# PickupDriverV3_3.net
KiCad netlist of a schematic drawn in EAGLE
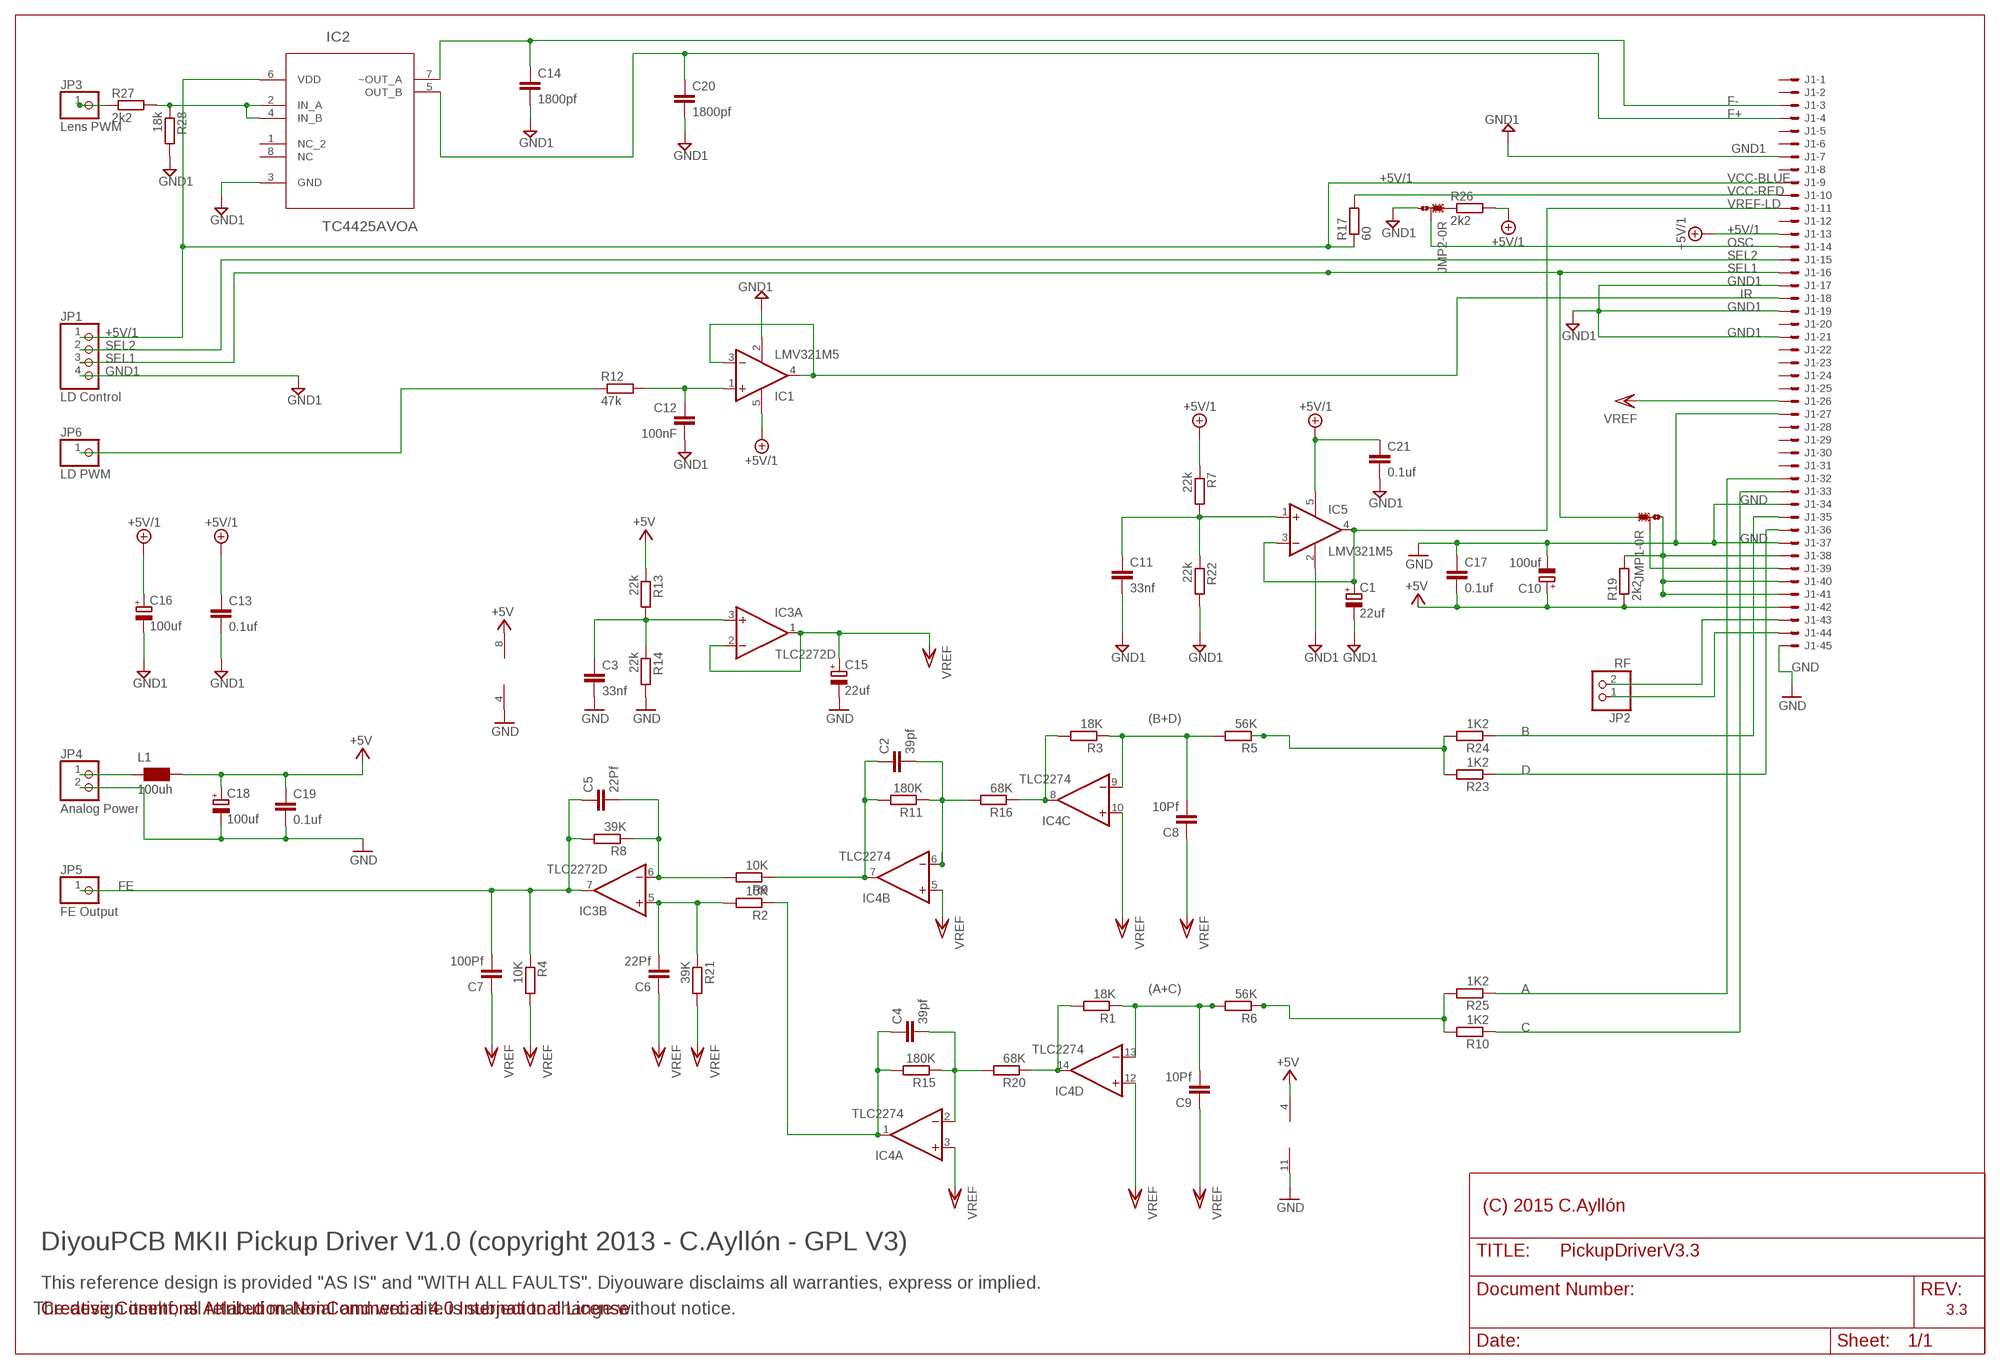
[diagram p0: schematic, sheet 1]

(export (version "E")
  (design (tool "Eeschema 10.0.6"))
  (components
    (comp (ref "C1")
      (value "22uf")
      (footprint "eagle-import:SMC_C")
      (libsource (lib "eagle-import") (part "CPOL-EUSMCC"))
    )
    (comp (ref "C2")
      (value "39pf")
      (footprint "eagle-import:C1206K")
      (libsource (lib "eagle-import") (part "C-EUC1206K"))
    )
    (comp (ref "C3")
      (value "33nf")
      (footprint "eagle-import:C1206K")
      (libsource (lib "eagle-import") (part "resistor_C-EUC1206K"))
    )
    (comp (ref "C4")
      (value "39pf")
      (footprint "eagle-import:C1206K")
      (libsource (lib "eagle-import") (part "C-EUC1206K"))
    )
    (comp (ref "C5")
      (value "22Pf")
      (footprint "eagle-import:C1206K")
      (libsource (lib "eagle-import") (part "C-EUC1206K"))
    )
    (comp (ref "C6")
      (value "22Pf")
      (footprint "eagle-import:C1206K")
      (libsource (lib "eagle-import") (part "C-EUC1206K"))
    )
    (comp (ref "C7")
      (value "100Pf")
      (footprint "eagle-import:C1206K")
      (libsource (lib "eagle-import") (part "C-EUC1206K"))
    )
    (comp (ref "C8")
      (value "10Pf")
      (footprint "eagle-import:C1206K")
      (libsource (lib "eagle-import") (part "C-EUC1206K"))
    )
    (comp (ref "C9")
      (value "10Pf")
      (footprint "eagle-import:C1206K")
      (libsource (lib "eagle-import") (part "C-EUC1206K"))
    )
    (comp (ref "C10")
      (value "100uf")
      (footprint "eagle-import:SMC_C")
      (libsource (lib "eagle-import") (part "CPOL-EUSMCC"))
    )
    (comp (ref "C11")
      (value "33nf")
      (footprint "eagle-import:C1206K")
      (libsource (lib "eagle-import") (part "resistor_C-EUC1206K"))
    )
    (comp (ref "C12")
      (value "100nF")
      (footprint "eagle-import:C1206K")
      (libsource (lib "eagle-import") (part "C-EUC1206K"))
    )
    (comp (ref "C13")
      (value "0.1uf")
      (footprint "eagle-import:C1206K")
      (libsource (lib "eagle-import") (part "resistor_C-EUC1206K"))
    )
    (comp (ref "C14")
      (value "1800pf")
      (footprint "eagle-import:C1206K")
      (libsource (lib "eagle-import") (part "C-EUC1206K"))
    )
    (comp (ref "C15")
      (value "22uf")
      (footprint "eagle-import:SMC_C")
      (libsource (lib "eagle-import") (part "CPOL-EUSMCC"))
    )
    (comp (ref "C16")
      (value "100uf")
      (footprint "eagle-import:SMC_C")
      (libsource (lib "eagle-import") (part "CPOL-EUSMCC"))
    )
    (comp (ref "C17")
      (value "0.1uf")
      (footprint "eagle-import:C1206K")
      (libsource (lib "eagle-import") (part "resistor_C-EUC1206K"))
    )
    (comp (ref "C18")
      (value "100uf")
      (footprint "eagle-import:SMC_C")
      (libsource (lib "eagle-import") (part "CPOL-EUSMCC"))
    )
    (comp (ref "C19")
      (value "0.1uf")
      (footprint "eagle-import:C1206K")
      (libsource (lib "eagle-import") (part "resistor_C-EUC1206K"))
    )
    (comp (ref "C20")
      (value "1800pf")
      (footprint "eagle-import:C1206K")
      (libsource (lib "eagle-import") (part "C-EUC1206K"))
    )
    (comp (ref "C21")
      (value "0.1uf")
      (footprint "eagle-import:C1206K")
      (libsource (lib "eagle-import") (part "resistor_C-EUC1206K"))
    )
    (comp (ref "IC1")
      (value "LMV321M5")
      (footprint "eagle-import:SOT23-5")
      (libsource (lib "eagle-import") (part "LMV321?M5"))
    )
    (comp (ref "IC2")
      (value "TC4425AVOA")
      (footprint "eagle-import:SOIC127P600X175-8N")
      (libsource (lib "eagle-import") (part "TC4425AVOA"))
    )
    (comp (ref "IC3")
      (value "TLC2272D")
      (footprint "eagle-import:SO08")
      (libsource (lib "eagle-import") (part "TLC2272D"))
    )
    (comp (ref "IC4")
      (value "TLC2274")
      (footprint "eagle-import:SO14")
      (libsource (lib "eagle-import") (part "TLC274D"))
    )
    (comp (ref "IC5")
      (value "LMV321M5")
      (footprint "eagle-import:SOT23-5")
      (libsource (lib "eagle-import") (part "LMV321?M5"))
    )
    (comp (ref "J1")
      (value "XF2H-4515-1LW")
      (footprint "eagle-import:XF2H-4515-1LW")
      (libsource (lib "eagle-import") (part "XF2-45?15-1LWH"))
    )
    (comp (ref "JMP1")
      (value "0R-JUMPA")
      (footprint "eagle-import:A0R-JMP")
      (libsource (lib "eagle-import") (part "0R-JUMPA"))
    )
    (comp (ref "JMP2")
      (value "0R-JUMPA")
      (footprint "eagle-import:A0R-JMP")
      (libsource (lib "eagle-import") (part "0R-JUMPA"))
    )
    (comp (ref "JP1")
      (value "LD Control")
      (footprint "eagle-import:1X04")
      (libsource (lib "eagle-import") (part "PINHD-1X4"))
    )
    (comp (ref "JP2")
      (value "RF")
      (footprint "eagle-import:1X02")
      (libsource (lib "eagle-import") (part "PINHD-1X2"))
    )
    (comp (ref "JP3")
      (value "Lens PWM")
      (footprint "eagle-import:1X01")
      (libsource (lib "eagle-import") (part "PINHD-1X1"))
    )
    (comp (ref "JP4")
      (value "Analog Power")
      (footprint "eagle-import:1X02")
      (libsource (lib "eagle-import") (part "PINHD-1X2"))
    )
    (comp (ref "JP5")
      (value "FE Output")
      (footprint "eagle-import:1X01")
      (libsource (lib "eagle-import") (part "PINHD-1X1"))
    )
    (comp (ref "JP6")
      (value "LD PWM")
      (footprint "eagle-import:1X01")
      (libsource (lib "eagle-import") (part "PINHD-1X1"))
    )
    (comp (ref "L1")
      (value "100uh")
      (footprint "eagle-import:CHOKE-100UH-1")
      (libsource (lib "eagle-import") (part "CHOKE-100UH"))
    )
    (comp (ref "R1")
      (value "18K")
      (footprint "eagle-import:R1206")
      (libsource (lib "eagle-import") (part "R-EU_R1206"))
    )
    (comp (ref "R2")
      (value "10K")
      (footprint "eagle-import:R1206")
      (libsource (lib "eagle-import") (part "R-EU_R1206"))
    )
    (comp (ref "R3")
      (value "18K")
      (footprint "eagle-import:R1206")
      (libsource (lib "eagle-import") (part "R-EU_R1206"))
    )
    (comp (ref "R4")
      (value "10K")
      (footprint "eagle-import:R1206")
      (libsource (lib "eagle-import") (part "R-EU_R1206"))
    )
    (comp (ref "R5")
      (value "56K")
      (footprint "eagle-import:R1206")
      (libsource (lib "eagle-import") (part "R-EU_R1206"))
    )
    (comp (ref "R6")
      (value "56K")
      (footprint "eagle-import:R1206")
      (libsource (lib "eagle-import") (part "R-EU_R1206"))
    )
    (comp (ref "R7")
      (value "22k")
      (footprint "eagle-import:R1206")
      (libsource (lib "eagle-import") (part "R-EU_R1206"))
    )
    (comp (ref "R8")
      (value "39K")
      (footprint "eagle-import:R1206")
      (libsource (lib "eagle-import") (part "R-EU_R1206"))
    )
    (comp (ref "R9")
      (value "10K")
      (footprint "eagle-import:R1206")
      (libsource (lib "eagle-import") (part "R-EU_R1206"))
    )
    (comp (ref "R10")
      (value "1K2")
      (footprint "eagle-import:R1206")
      (libsource (lib "eagle-import") (part "R-EU_R1206"))
    )
    (comp (ref "R11")
      (value "180K")
      (footprint "eagle-import:R1206")
      (libsource (lib "eagle-import") (part "R-EU_R1206"))
    )
    (comp (ref "R12")
      (value "47k")
      (footprint "eagle-import:R1206")
      (libsource (lib "eagle-import") (part "R-EU_R1206"))
    )
    (comp (ref "R13")
      (value "22k")
      (footprint "eagle-import:R1206")
      (libsource (lib "eagle-import") (part "R-EU_R1206"))
    )
    (comp (ref "R14")
      (value "22k")
      (footprint "eagle-import:R1206")
      (libsource (lib "eagle-import") (part "R-EU_R1206"))
    )
    (comp (ref "R15")
      (value "180K")
      (footprint "eagle-import:R1206")
      (libsource (lib "eagle-import") (part "R-EU_R1206"))
    )
    (comp (ref "R16")
      (value "68K")
      (footprint "eagle-import:R1206")
      (libsource (lib "eagle-import") (part "R-EU_R1206"))
    )
    (comp (ref "R17")
      (value "60")
      (footprint "eagle-import:R1206")
      (libsource (lib "eagle-import") (part "R-EU_R1206"))
    )
    (comp (ref "R19")
      (value "2k2")
      (footprint "eagle-import:R1206")
      (libsource (lib "eagle-import") (part "R-EU_R1206"))
    )
    (comp (ref "R20")
      (value "68K")
      (footprint "eagle-import:R1206")
      (libsource (lib "eagle-import") (part "R-EU_R1206"))
    )
    (comp (ref "R21")
      (value "39K")
      (footprint "eagle-import:R1206")
      (libsource (lib "eagle-import") (part "R-EU_R1206"))
    )
    (comp (ref "R22")
      (value "22k")
      (footprint "eagle-import:R1206")
      (libsource (lib "eagle-import") (part "R-EU_R1206"))
    )
    (comp (ref "R23")
      (value "1K2")
      (footprint "eagle-import:R1206")
      (libsource (lib "eagle-import") (part "R-EU_R1206"))
    )
    (comp (ref "R24")
      (value "1K2")
      (footprint "eagle-import:R1206")
      (libsource (lib "eagle-import") (part "R-EU_R1206"))
    )
    (comp (ref "R25")
      (value "1K2")
      (footprint "eagle-import:R1206")
      (libsource (lib "eagle-import") (part "R-EU_R1206"))
    )
    (comp (ref "R26")
      (value "2k2")
      (footprint "eagle-import:R1206")
      (libsource (lib "eagle-import") (part "R-EU_R1206"))
    )
    (comp (ref "R27")
      (value "2k2")
      (footprint "eagle-import:R1206")
      (libsource (lib "eagle-import") (part "R-EU_R1206"))
    )
    (comp (ref "R28")
      (value "18k")
      (footprint "eagle-import:R1206")
      (libsource (lib "eagle-import") (part "R-EU_R1206"))
    )
  )
  (nets
    (net (code "1") (name "+5V") (class "Default")
      (node (ref "C10") (pin "+") (pinfunction "+_+") (pintype "passive"))
      (node (ref "C17") (pin "2") (pinfunction "2_2") (pintype "passive"))
      (node (ref "C18") (pin "+") (pinfunction "+_+") (pintype "passive"))
      (node (ref "C19") (pin "1") (pinfunction "1_1") (pintype "passive"))
      (node (ref "IC3") (pin "8") (pinfunction "V+_8") (pintype "power_in"))
      (node (ref "IC4") (pin "4") (pinfunction "V+_4") (pintype "power_in"))
      (node (ref "J1") (pin "42") (pinfunction "MS_42") (pintype "passive"))
      (node (ref "L1") (pin "2") (pinfunction "2_2") (pintype "passive"))
      (node (ref "R13") (pin "1") (pinfunction "1_1") (pintype "passive"))
      (node (ref "R19") (pin "1") (pinfunction "1_1") (pintype "passive"))
    )
    (net (code "2") (name "+5V{slash}1") (class "Default")
      (node (ref "C13") (pin "1") (pinfunction "1_1") (pintype "passive"))
      (node (ref "C16") (pin "+") (pinfunction "+_+") (pintype "passive"))
      (node (ref "C21") (pin "1") (pinfunction "1_1") (pintype "passive"))
      (node (ref "IC1") (pin "5") (pinfunction "V+_5") (pintype "power_in"))
      (node (ref "IC2") (pin "6") (pinfunction "VDD_6") (pintype "power_in"))
      (node (ref "IC5") (pin "5") (pinfunction "V+_5") (pintype "power_in"))
      (node (ref "J1") (pin "13") (pinfunction "MS_13") (pintype "passive"))
      (node (ref "J1") (pin "9") (pinfunction "MS_9") (pintype "passive"))
      (node (ref "JP1") (pin "1") (pinfunction "1_1") (pintype "passive"))
      (node (ref "R17") (pin "1") (pinfunction "1_1") (pintype "passive"))
      (node (ref "R26") (pin "2") (pinfunction "2_2") (pintype "passive"))
      (node (ref "R7") (pin "1") (pinfunction "1_1") (pintype "passive"))
    )
    (net (code "3") (name "/A") (class "Default")
      (node (ref "J1") (pin "32") (pinfunction "MS_32") (pintype "passive"))
      (node (ref "R25") (pin "1") (pinfunction "1_1") (pintype "passive"))
    )
    (net (code "4") (name "/B") (class "Default")
      (node (ref "J1") (pin "35") (pinfunction "MS_35") (pintype "passive"))
      (node (ref "R24") (pin "1") (pinfunction "1_1") (pintype "passive"))
    )
    (net (code "5") (name "/C") (class "Default")
      (node (ref "J1") (pin "33") (pinfunction "MS_33") (pintype "passive"))
      (node (ref "R10") (pin "1") (pinfunction "1_1") (pintype "passive"))
    )
    (net (code "6") (name "/D") (class "Default")
      (node (ref "J1") (pin "36") (pinfunction "MS_36") (pintype "passive"))
      (node (ref "R23") (pin "1") (pinfunction "1_1") (pintype "passive"))
    )
    (net (code "7") (name "/F+") (class "Default")
      (node (ref "C20") (pin "1") (pinfunction "1_1") (pintype "passive"))
      (node (ref "IC2") (pin "5") (pinfunction "OUT_B_5") (pintype "output"))
      (node (ref "J1") (pin "4") (pinfunction "MS_4") (pintype "passive"))
    )
    (net (code "8") (name "/F-") (class "Default")
      (node (ref "C14") (pin "1") (pinfunction "1_1") (pintype "passive"))
      (node (ref "IC2") (pin "7") (pinfunction "~{OUT_A}_7") (pintype "output"))
      (node (ref "J1") (pin "3") (pinfunction "MS_3") (pintype "passive"))
    )
    (net (code "9") (name "/FE") (class "Default")
      (node (ref "C5") (pin "1") (pinfunction "1_1") (pintype "passive"))
      (node (ref "C7") (pin "2") (pinfunction "2_2") (pintype "passive"))
      (node (ref "IC3") (pin "7") (pinfunction "OUT_7") (pintype "output"))
      (node (ref "JP5") (pin "1") (pinfunction "1_1") (pintype "passive"))
      (node (ref "R4") (pin "1") (pinfunction "1_1") (pintype "passive"))
      (node (ref "R8") (pin "2") (pinfunction "2_2") (pintype "passive"))
    )
    (net (code "10") (name "/IR") (class "Default")
      (node (ref "IC1") (pin "3") (pinfunction "-IN_3") (pintype "input"))
      (node (ref "IC1") (pin "4") (pinfunction "OUT_4") (pintype "output"))
      (node (ref "J1") (pin "18") (pinfunction "MS_18") (pintype "passive"))
    )
    (net (code "11") (name "/OSC") (class "Default")
      (node (ref "J1") (pin "14") (pinfunction "MS_14") (pintype "passive"))
      (node (ref "JMP2") (pin "2") (pinfunction "2_2") (pintype "passive"))
    )
    (net (code "12") (name "/SEL1") (class "Default")
      (node (ref "J1") (pin "16") (pinfunction "MS_16") (pintype "passive"))
      (node (ref "JMP1") (pin "1") (pinfunction "1_1") (pintype "passive"))
      (node (ref "JP1") (pin "3") (pinfunction "3_3") (pintype "passive"))
    )
    (net (code "13") (name "/SEL2") (class "Default")
      (node (ref "J1") (pin "15") (pinfunction "MS_15") (pintype "passive"))
      (node (ref "JP1") (pin "2") (pinfunction "2_2") (pintype "passive"))
    )
    (net (code "14") (name "/VREF-LD") (class "Default")
      (node (ref "C1") (pin "+") (pinfunction "+_+") (pintype "passive"))
      (node (ref "IC5") (pin "3") (pinfunction "-IN_3") (pintype "input"))
      (node (ref "IC5") (pin "4") (pinfunction "OUT_4") (pintype "output"))
      (node (ref "J1") (pin "11") (pinfunction "MS_11") (pintype "passive"))
    )
    (net (code "15") (name "GND") (class "Default")
      (node (ref "C10") (pin "-") (pinfunction "-_-") (pintype "passive"))
      (node (ref "C15") (pin "-") (pinfunction "-_-") (pintype "passive"))
      (node (ref "C17") (pin "1") (pinfunction "1_1") (pintype "passive"))
      (node (ref "C18") (pin "-") (pinfunction "-_-") (pintype "passive"))
      (node (ref "C19") (pin "2") (pinfunction "2_2") (pintype "passive"))
      (node (ref "C3") (pin "2") (pinfunction "2_2") (pintype "passive"))
      (node (ref "IC3") (pin "4") (pinfunction "V-_4") (pintype "power_in"))
      (node (ref "IC4") (pin "11") (pinfunction "V-_11") (pintype "power_in"))
      (node (ref "J1") (pin "27") (pinfunction "MS_27") (pintype "passive"))
      (node (ref "J1") (pin "34") (pinfunction "MS_34") (pintype "passive"))
      (node (ref "J1") (pin "37") (pinfunction "MS_37") (pintype "passive"))
      (node (ref "J1") (pin "45") (pinfunction "MS_45") (pintype "passive"))
      (node (ref "JP4") (pin "2") (pinfunction "2_2") (pintype "passive"))
      (node (ref "R14") (pin "2") (pinfunction "2_2") (pintype "passive"))
    )
    (net (code "16") (name "GND1") (class "Default")
      (node (ref "C1") (pin "-") (pinfunction "-_-") (pintype "passive"))
      (node (ref "C11") (pin "2") (pinfunction "2_2") (pintype "passive"))
      (node (ref "C12") (pin "2") (pinfunction "2_2") (pintype "passive"))
      (node (ref "C13") (pin "2") (pinfunction "2_2") (pintype "passive"))
      (node (ref "C14") (pin "2") (pinfunction "2_2") (pintype "passive"))
      (node (ref "C16") (pin "-") (pinfunction "-_-") (pintype "passive"))
      (node (ref "C20") (pin "2") (pinfunction "2_2") (pintype "passive"))
      (node (ref "C21") (pin "2") (pinfunction "2_2") (pintype "passive"))
      (node (ref "IC1") (pin "2") (pinfunction "V-_2") (pintype "power_in"))
      (node (ref "IC2") (pin "3") (pinfunction "GND_3") (pintype "passive"))
      (node (ref "IC5") (pin "2") (pinfunction "V-_2") (pintype "power_in"))
      (node (ref "J1") (pin "17") (pinfunction "MS_17") (pintype "passive"))
      (node (ref "J1") (pin "19") (pinfunction "MS_19") (pintype "passive"))
      (node (ref "J1") (pin "21") (pinfunction "MS_21") (pintype "passive"))
      (node (ref "J1") (pin "7") (pinfunction "MS_7") (pintype "passive"))
      (node (ref "JMP2") (pin "3") (pinfunction "3_3") (pintype "passive"))
      (node (ref "JP1") (pin "4") (pinfunction "4_4") (pintype "passive"))
      (node (ref "R22") (pin "2") (pinfunction "2_2") (pintype "passive"))
      (node (ref "R28") (pin "2") (pinfunction "2_2") (pintype "passive"))
    )
    (net (code "17") (name "Net-(IC1-+IN)") (class "Default")
      (node (ref "C12") (pin "1") (pinfunction "1_1") (pintype "passive"))
      (node (ref "IC1") (pin "1") (pinfunction "+IN_1") (pintype "input"))
      (node (ref "R12") (pin "2") (pinfunction "2_2") (pintype "passive"))
    )
    (net (code "18") (name "Net-(IC2-IN_A)") (class "Default")
      (node (ref "IC2") (pin "2") (pinfunction "IN_A_2") (pintype "input"))
      (node (ref "IC2") (pin "4") (pinfunction "IN_B_4") (pintype "input"))
      (node (ref "R27") (pin "2") (pinfunction "2_2") (pintype "passive"))
      (node (ref "R28") (pin "1") (pinfunction "1_1") (pintype "passive"))
    )
    (net (code "19") (name "Net-(IC3A-+IN)") (class "Default")
      (node (ref "C3") (pin "1") (pinfunction "1_1") (pintype "passive"))
      (node (ref "IC3") (pin "3") (pinfunction "+IN_3") (pintype "input"))
      (node (ref "R13") (pin "2") (pinfunction "2_2") (pintype "passive"))
      (node (ref "R14") (pin "1") (pinfunction "1_1") (pintype "passive"))
    )
    (net (code "20") (name "Net-(IC3B-+IN)") (class "Default")
      (node (ref "C6") (pin "2") (pinfunction "2_2") (pintype "passive"))
      (node (ref "IC3") (pin "5") (pinfunction "+IN_5") (pintype "input"))
      (node (ref "R2") (pin "2") (pinfunction "2_2") (pintype "passive"))
      (node (ref "R21") (pin "1") (pinfunction "1_1") (pintype "passive"))
    )
    (net (code "21") (name "Net-(IC3B--IN)") (class "Default")
      (node (ref "C5") (pin "2") (pinfunction "2_2") (pintype "passive"))
      (node (ref "IC3") (pin "6") (pinfunction "-IN_6") (pintype "input"))
      (node (ref "R8") (pin "1") (pinfunction "1_1") (pintype "passive"))
      (node (ref "R9") (pin "2") (pinfunction "2_2") (pintype "passive"))
    )
    (net (code "22") (name "Net-(IC4A--IN)") (class "Default")
      (node (ref "C4") (pin "2") (pinfunction "2_2") (pintype "passive"))
      (node (ref "IC4") (pin "2") (pinfunction "-IN_2") (pintype "input"))
      (node (ref "R15") (pin "1") (pinfunction "1_1") (pintype "passive"))
      (node (ref "R20") (pin "2") (pinfunction "2_2") (pintype "passive"))
    )
    (net (code "23") (name "Net-(IC4A-OUT)") (class "Default")
      (node (ref "C4") (pin "1") (pinfunction "1_1") (pintype "passive"))
      (node (ref "IC4") (pin "1") (pinfunction "OUT_1") (pintype "output"))
      (node (ref "R15") (pin "2") (pinfunction "2_2") (pintype "passive"))
      (node (ref "R2") (pin "1") (pinfunction "1_1") (pintype "passive"))
    )
    (net (code "24") (name "Net-(IC4B--IN)") (class "Default")
      (node (ref "C2") (pin "2") (pinfunction "2_2") (pintype "passive"))
      (node (ref "IC4") (pin "6") (pinfunction "-IN_6") (pintype "input"))
      (node (ref "R11") (pin "1") (pinfunction "1_1") (pintype "passive"))
      (node (ref "R16") (pin "2") (pinfunction "2_2") (pintype "passive"))
    )
    (net (code "25") (name "Net-(IC4B-OUT)") (class "Default")
      (node (ref "C2") (pin "1") (pinfunction "1_1") (pintype "passive"))
      (node (ref "IC4") (pin "7") (pinfunction "OUT_7") (pintype "output"))
      (node (ref "R11") (pin "2") (pinfunction "2_2") (pintype "passive"))
      (node (ref "R9") (pin "1") (pinfunction "1_1") (pintype "passive"))
    )
    (net (code "26") (name "Net-(IC4C--IN)") (class "Default")
      (node (ref "C8") (pin "2") (pinfunction "2_2") (pintype "passive"))
      (node (ref "IC4") (pin "9") (pinfunction "-IN_9") (pintype "input"))
      (node (ref "R3") (pin "1") (pinfunction "1_1") (pintype "passive"))
      (node (ref "R5") (pin "2") (pinfunction "2_2") (pintype "passive"))
    )
    (net (code "27") (name "Net-(IC4C-OUT)") (class "Default")
      (node (ref "IC4") (pin "8") (pinfunction "OUT_8") (pintype "output"))
      (node (ref "R16") (pin "1") (pinfunction "1_1") (pintype "passive"))
      (node (ref "R3") (pin "2") (pinfunction "2_2") (pintype "passive"))
    )
    (net (code "28") (name "Net-(IC4D--IN)") (class "Default")
      (node (ref "C9") (pin "2") (pinfunction "2_2") (pintype "passive"))
      (node (ref "IC4") (pin "13") (pinfunction "-IN_13") (pintype "input"))
      (node (ref "R1") (pin "1") (pinfunction "1_1") (pintype "passive"))
      (node (ref "R6") (pin "2") (pinfunction "2_2") (pintype "passive"))
    )
    (net (code "29") (name "Net-(IC4D-OUT)") (class "Default")
      (node (ref "IC4") (pin "14") (pinfunction "OUT_14") (pintype "output"))
      (node (ref "R1") (pin "2") (pinfunction "2_2") (pintype "passive"))
      (node (ref "R20") (pin "1") (pinfunction "1_1") (pintype "passive"))
    )
    (net (code "30") (name "Net-(IC5-+IN)") (class "Default")
      (node (ref "C11") (pin "1") (pinfunction "1_1") (pintype "passive"))
      (node (ref "IC5") (pin "1") (pinfunction "+IN_1") (pintype "input"))
      (node (ref "R22") (pin "1") (pinfunction "1_1") (pintype "passive"))
      (node (ref "R7") (pin "2") (pinfunction "2_2") (pintype "passive"))
    )
    (net (code "31") (name "Net-(J1AF-MS)") (class "Default")
      (node (ref "J1") (pin "38") (pinfunction "MS_38") (pintype "passive"))
      (node (ref "J1") (pin "40") (pinfunction "MS_40") (pintype "passive"))
      (node (ref "J1") (pin "41") (pinfunction "MS_41") (pintype "passive"))
      (node (ref "JMP1") (pin "3") (pinfunction "3_3") (pintype "passive"))
      (node (ref "R19") (pin "2") (pinfunction "2_2") (pintype "passive"))
    )
    (net (code "32") (name "Net-(J1AG-MS)") (class "Default")
      (node (ref "J1") (pin "39") (pinfunction "MS_39") (pintype "passive"))
      (node (ref "JMP1") (pin "2") (pinfunction "2_2") (pintype "passive"))
    )
    (net (code "33") (name "Net-(J1AL-MS)") (class "Default")
      (node (ref "J1") (pin "43") (pinfunction "MS_43") (pintype "passive"))
      (node (ref "JP2") (pin "2") (pinfunction "2_2") (pintype "passive"))
    )
    (net (code "34") (name "Net-(J1AM-MS)") (class "Default")
      (node (ref "J1") (pin "44") (pinfunction "MS_44") (pintype "passive"))
      (node (ref "JP2") (pin "1") (pinfunction "1_1") (pintype "passive"))
    )
    (net (code "35") (name "Net-(J1B-MS)") (class "Default")
      (node (ref "J1") (pin "10") (pinfunction "MS_10") (pintype "passive"))
      (node (ref "R17") (pin "2") (pinfunction "2_2") (pintype "passive"))
    )
    (net (code "36") (name "Net-(JMP2-Pad1)") (class "Default")
      (node (ref "JMP2") (pin "1") (pinfunction "1_1") (pintype "passive"))
      (node (ref "R26") (pin "1") (pinfunction "1_1") (pintype "passive"))
    )
    (net (code "37") (name "Net-(JP3-Pad1)") (class "Default")
      (node (ref "JP3") (pin "1") (pinfunction "1_1") (pintype "passive"))
      (node (ref "R27") (pin "1") (pinfunction "1_1") (pintype "passive"))
    )
    (net (code "38") (name "Net-(JP4-Pad1)") (class "Default")
      (node (ref "JP4") (pin "1") (pinfunction "1_1") (pintype "passive"))
      (node (ref "L1") (pin "1") (pinfunction "1_1") (pintype "passive"))
    )
    (net (code "39") (name "Net-(JP6-Pad1)") (class "Default")
      (node (ref "JP6") (pin "1") (pinfunction "1_1") (pintype "passive"))
      (node (ref "R12") (pin "1") (pinfunction "1_1") (pintype "passive"))
    )
    (net (code "40") (name "Net-(R10-Pad2)") (class "Default")
      (node (ref "R10") (pin "2") (pinfunction "2_2") (pintype "passive"))
      (node (ref "R25") (pin "2") (pinfunction "2_2") (pintype "passive"))
      (node (ref "R6") (pin "1") (pinfunction "1_1") (pintype "passive"))
    )
    (net (code "41") (name "Net-(R23-Pad2)") (class "Default")
      (node (ref "R23") (pin "2") (pinfunction "2_2") (pintype "passive"))
      (node (ref "R24") (pin "2") (pinfunction "2_2") (pintype "passive"))
      (node (ref "R5") (pin "1") (pinfunction "1_1") (pintype "passive"))
    )
    (net (code "42") (name "VREF") (class "Default")
      (node (ref "C15") (pin "+") (pinfunction "+_+") (pintype "passive"))
      (node (ref "C6") (pin "1") (pinfunction "1_1") (pintype "passive"))
      (node (ref "C7") (pin "1") (pinfunction "1_1") (pintype "passive"))
      (node (ref "C8") (pin "1") (pinfunction "1_1") (pintype "passive"))
      (node (ref "C9") (pin "1") (pinfunction "1_1") (pintype "passive"))
      (node (ref "IC3") (pin "1") (pinfunction "OUT_1") (pintype "output"))
      (node (ref "IC3") (pin "2") (pinfunction "-IN_2") (pintype "input"))
      (node (ref "IC4") (pin "10") (pinfunction "+IN_10") (pintype "input"))
      (node (ref "IC4") (pin "12") (pinfunction "+IN_12") (pintype "input"))
      (node (ref "IC4") (pin "3") (pinfunction "+IN_3") (pintype "input"))
      (node (ref "IC4") (pin "5") (pinfunction "+IN_5") (pintype "input"))
      (node (ref "J1") (pin "26") (pinfunction "MS_26") (pintype "passive"))
      (node (ref "R21") (pin "2") (pinfunction "2_2") (pintype "passive"))
      (node (ref "R4") (pin "2") (pinfunction "2_2") (pintype "passive"))
    )
    (net (code "43") (name "unconnected-(IC2-NC-Pad8)") (class "Default")
      (node (ref "IC2") (pin "8") (pinfunction "NC_8") (pintype "no_connect"))
    )
    (net (code "44") (name "unconnected-(IC2-NC_2-Pad1)") (class "Default")
      (node (ref "IC2") (pin "1") (pinfunction "NC_2_1") (pintype "no_connect"))
    )
    (net (code "45") (name "unconnected-(J1A-MSV-Pad1)") (class "Default")
      (node (ref "J1") (pin "1") (pinfunction "MSV_1") (pintype "passive"))
    )
    (net (code "46") (name "unconnected-(J1AO-MS-Pad5)") (class "Default")
      (node (ref "J1") (pin "5") (pinfunction "MS_5") (pintype "passive"))
    )
    (net (code "47") (name "unconnected-(J1AP-MS-Pad6)") (class "Default")
      (node (ref "J1") (pin "6") (pinfunction "MS_6") (pintype "passive"))
    )
    (net (code "48") (name "unconnected-(J1AR-MS-Pad8)") (class "Default")
      (node (ref "J1") (pin "8") (pinfunction "MS_8") (pintype "passive"))
    )
    (net (code "49") (name "unconnected-(J1D-MS-Pad12)") (class "Default")
      (node (ref "J1") (pin "12") (pinfunction "MS_12") (pintype "passive"))
    )
    (net (code "50") (name "unconnected-(J1L-MS-Pad2)") (class "Default")
      (node (ref "J1") (pin "2") (pinfunction "MS_2") (pintype "passive"))
    )
    (net (code "51") (name "unconnected-(J1M-MS-Pad20)") (class "Default")
      (node (ref "J1") (pin "20") (pinfunction "MS_20") (pintype "passive"))
    )
    (net (code "52") (name "unconnected-(J1O-MS-Pad22)") (class "Default")
      (node (ref "J1") (pin "22") (pinfunction "MS_22") (pintype "passive"))
    )
    (net (code "53") (name "unconnected-(J1P-MS-Pad23)") (class "Default")
      (node (ref "J1") (pin "23") (pinfunction "MS_23") (pintype "passive"))
    )
    (net (code "54") (name "unconnected-(J1Q-MS-Pad24)") (class "Default")
      (node (ref "J1") (pin "24") (pinfunction "MS_24") (pintype "passive"))
    )
    (net (code "55") (name "unconnected-(J1R-MS-Pad25)") (class "Default")
      (node (ref "J1") (pin "25") (pinfunction "MS_25") (pintype "passive"))
    )
    (net (code "56") (name "unconnected-(J1U-MS-Pad28)") (class "Default")
      (node (ref "J1") (pin "28") (pinfunction "MS_28") (pintype "passive"))
    )
    (net (code "57") (name "unconnected-(J1V-MS-Pad29)") (class "Default")
      (node (ref "J1") (pin "29") (pinfunction "MS_29") (pintype "passive"))
    )
    (net (code "58") (name "unconnected-(J1X-MS-Pad30)") (class "Default")
      (node (ref "J1") (pin "30") (pinfunction "MS_30") (pintype "passive"))
    )
    (net (code "59") (name "unconnected-(J1Y-MS-Pad31)") (class "Default")
      (node (ref "J1") (pin "31") (pinfunction "MS_31") (pintype "passive"))
    )
  )
)
